# 1_P1.net
KiCad netlist of a schematic drawn in Altium Designer
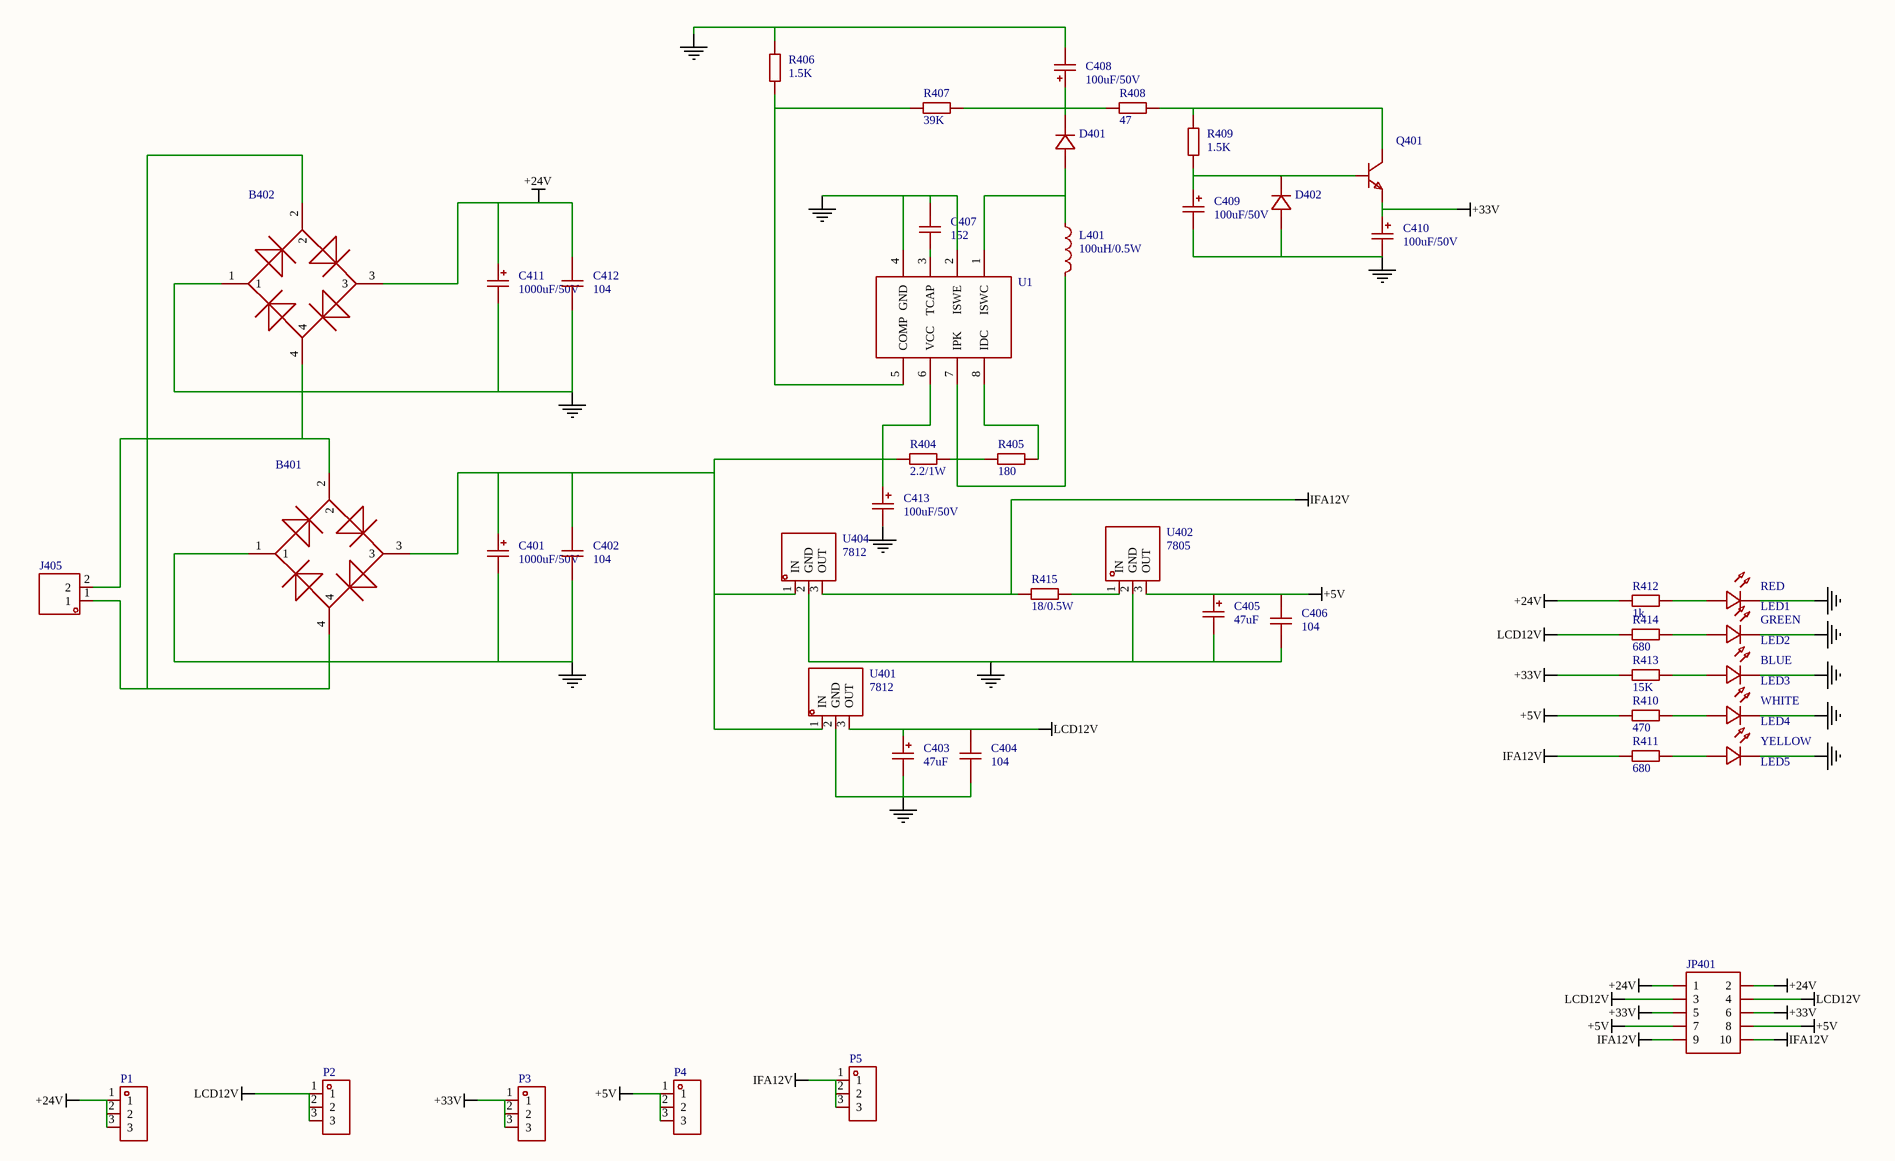
[diagram p0: 1_P1.schdoc]

(export (version "E")
  (design (tool "Eeschema 10.0.6"))
  (components
    (comp (ref "B401")
      (value "~")
      (footprint "B401/B402")
      (libsource (lib "altium-import") (part "root_0_整流桥_"))
    )
    (comp (ref "B402")
      (value "~")
      (footprint "B401/B402")
      (libsource (lib "altium-import") (part "root_0_整流桥_"))
    )
    (comp (ref "C401")
      (value "1000uF/50V")
      (footprint "C401/C411")
      (libsource (lib "altium-import") (part "root_1_C_Ele_SMD_3x5.4mm_"))
    )
    (comp (ref "C402")
      (value "104")
      (footprint "RAD-0.2")
      (libsource (lib "altium-import") (part "root_1_CAP_0603_"))
    )
    (comp (ref "C403")
      (value "47uF")
      (footprint "电解电容")
      (libsource (lib "altium-import") (part "root_1_C_Ele_SMD_3x5.4mm_"))
    )
    (comp (ref "C404")
      (value "104")
      (footprint "RAD-0.2")
      (libsource (lib "altium-import") (part "root_1_CAP_0603_"))
    )
    (comp (ref "C405")
      (value "47uF")
      (footprint "电解电容")
      (libsource (lib "altium-import") (part "root_1_C_Ele_SMD_3x5.4mm_"))
    )
    (comp (ref "C406")
      (value "104")
      (footprint "RAD-0.2")
      (libsource (lib "altium-import") (part "root_1_CAP_0603_"))
    )
    (comp (ref "C407")
      (value "152")
      (footprint "RAD-0.2")
      (libsource (lib "altium-import") (part "root_1_CAP_0603_"))
    )
    (comp (ref "C408")
      (value "100uF/50V")
      (footprint "电解电容")
      (libsource (lib "altium-import") (part "root_3_C_Ele_SMD_3x5.4mm_"))
    )
    (comp (ref "C409")
      (value "100uF/50V")
      (footprint "电解电容")
      (libsource (lib "altium-import") (part "root_1_C_Ele_SMD_3x5.4mm_"))
    )
    (comp (ref "C410")
      (value "100uF/50V")
      (footprint "电解电容")
      (libsource (lib "altium-import") (part "root_1_C_Ele_SMD_3x5.4mm_"))
    )
    (comp (ref "C411")
      (value "1000uF/50V")
      (footprint "C401/C411")
      (libsource (lib "altium-import") (part "root_1_C_Ele_SMD_3x5.4mm_"))
    )
    (comp (ref "C412")
      (value "104")
      (footprint "RAD-0.2")
      (libsource (lib "altium-import") (part "root_1_CAP_0603_"))
    )
    (comp (ref "C413")
      (value "100uF/50V")
      (footprint "电解电容")
      (libsource (lib "altium-import") (part "root_1_C_Ele_SMD_3x5.4mm_"))
    )
    (comp (ref "D401")
      (value "~")
      (footprint "D401/D402")
      (libsource (lib "altium-import") (part "root_1_D_1N4007A_"))
    )
    (comp (ref "D402")
      (value "~")
      (footprint "D401/D402")
      (libsource (lib "altium-import") (part "root_1_D_1N4007A_"))
    )
    (comp (ref "J405")
      (value "~")
      (footprint "J405")
      (fields (field (name "MANUFACTURER") "Ckmtw(灿科盟)") (field (name "MANUFACTURER PART") "B-2100S02P-A110"))
      (libsource (lib "altium-import") (part "root_2_HDR-M_2.54_1x2P_"))
    )
    (comp (ref "JP401")
      (value "~")
      (footprint "JP401")
      (libsource (lib "altium-import") (part "root_0_HDR-F_2.54_2x5_"))
    )
    (comp (ref "L401")
      (value "100uH/0.5W")
      (footprint "L401")
      (libsource (lib "altium-import") (part "root_3_L_0603_"))
    )
    (comp (ref "LED1")
      (value "RED")
      (footprint "LED")
      (libsource (lib "altium-import") (part "root_0_LED_TH-R_3mm_"))
    )
    (comp (ref "LED2")
      (value "GREEN")
      (footprint "LED")
      (libsource (lib "altium-import") (part "root_0_LED_TH-R_3mm_"))
    )
    (comp (ref "LED3")
      (value "BLUE")
      (footprint "LED")
      (libsource (lib "altium-import") (part "root_0_LED_TH-R_3mm_"))
    )
    (comp (ref "LED4")
      (value "WHITE")
      (footprint "LED")
      (libsource (lib "altium-import") (part "root_0_LED_TH-R_3mm_"))
    )
    (comp (ref "LED5")
      (value "YELLOW")
      (footprint "LED")
      (libsource (lib "altium-import") (part "root_0_LED_TH-R_3mm_"))
    )
    (comp (ref "P1")
      (value "~")
      (footprint "HDR-TH_3P-P2.54-V-F")
      (libsource (lib "altium-import") (part "root_0_HDR-F_2.54_1x3P_"))
    )
    (comp (ref "P2")
      (value "~")
      (footprint "HDR-TH_3P-P2.54-V-F")
      (libsource (lib "altium-import") (part "root_0_HDR-F_2.54_1x3P_"))
    )
    (comp (ref "P3")
      (value "~")
      (footprint "HDR-TH_3P-P2.54-V-F")
      (libsource (lib "altium-import") (part "root_0_HDR-F_2.54_1x3P_"))
    )
    (comp (ref "P4")
      (value "~")
      (footprint "HDR-TH_3P-P2.54-V-F")
      (libsource (lib "altium-import") (part "root_0_HDR-F_2.54_1x3P_"))
    )
    (comp (ref "P5")
      (value "~")
      (footprint "HDR-TH_3P-P2.54-V-F")
      (libsource (lib "altium-import") (part "root_0_HDR-F_2.54_1x3P_"))
    )
    (comp (ref "Q401")
      (value "~")
      (footprint "Q401")
      (libsource (lib "altium-import") (part "root_0_S8050_SOT_NPN_"))
    )
    (comp (ref "R404")
      (value "2.2/1W")
      (footprint "Res_1/2W")
      (libsource (lib "altium-import") (part "root_2_Res_AXIAL-1/4W_"))
    )
    (comp (ref "R405")
      (value "180")
      (footprint "Res_1/4W")
      (libsource (lib "altium-import") (part "root_0_Res_AXIAL-1/4W_"))
    )
    (comp (ref "R406")
      (value "1.5K")
      (footprint "Res_1/4W")
      (libsource (lib "altium-import") (part "root_1_Res_AXIAL-1/4W_"))
    )
    (comp (ref "R407")
      (value "39K")
      (footprint "Res_1/4W")
      (libsource (lib "altium-import") (part "root_0_Res_AXIAL-1/4W_"))
    )
    (comp (ref "R408")
      (value "47")
      (footprint "Res_1/4W")
      (libsource (lib "altium-import") (part "root_0_Res_AXIAL-1/4W_"))
    )
    (comp (ref "R409")
      (value "1.5K")
      (footprint "Res_1/4W")
      (libsource (lib "altium-import") (part "root_1_Res_AXIAL-1/4W_"))
    )
    (comp (ref "R410")
      (value "470")
      (footprint "Res_1/4W")
      (libsource (lib "altium-import") (part "root_0_Res_AXIAL-1/4W_"))
    )
    (comp (ref "R411")
      (value "680")
      (footprint "Res_1/4W")
      (libsource (lib "altium-import") (part "root_0_Res_AXIAL-1/4W_"))
    )
    (comp (ref "R412")
      (value "1k")
      (footprint "Res_1/4W")
      (libsource (lib "altium-import") (part "root_0_Res_AXIAL-1/4W_"))
    )
    (comp (ref "R413")
      (value "15K")
      (footprint "Res_1/4W")
      (libsource (lib "altium-import") (part "root_0_Res_AXIAL-1/4W_"))
    )
    (comp (ref "R414")
      (value "680")
      (footprint "Res_1/4W")
      (libsource (lib "altium-import") (part "root_0_Res_AXIAL-1/4W_"))
    )
    (comp (ref "R415")
      (value "18/0.5W")
      (footprint "Res_1/2W")
      (libsource (lib "altium-import") (part "root_2_Res_AXIAL-1/4W_"))
    )
    (comp (ref "U1")
      (value "~")
      (footprint "DIP-8_L10.0-W6.5-P2.54-LS7.6-BL-A")
      (libsource (lib "altium-import") (part "root_1_MC34063_"))
    )
    (comp (ref "U401")
      (value "7812")
      (footprint "U401/U402/U404")
      (fields (field (name "MANUFACTURER") "BLUE ROCKET(蓝箭)"))
      (libsource (lib "altium-import") (part "root_1_7812_"))
    )
    (comp (ref "U402")
      (value "7805")
      (footprint "U401/U402/U404")
      (fields (field (name "MANUFACTURER") "SY(顺烨）"))
      (libsource (lib "altium-import") (part "root_1_7805_"))
    )
    (comp (ref "U404")
      (value "7812")
      (footprint "U401/U402/U404")
      (fields (field (name "MANUFACTURER") "BLUE ROCKET(蓝箭)"))
      (libsource (lib "altium-import") (part "root_1_7812_"))
    )
  )
  (nets
    (net (code "1") (name "+5V") (class "Default")
      (node (ref "C405") (pin "1") (pinfunction "1_1") (pintype "passive"))
      (node (ref "C406") (pin "2") (pinfunction "2_2") (pintype "passive"))
      (node (ref "JP401") (pin "7") (pinfunction "7_7") (pintype "passive"))
      (node (ref "JP401") (pin "8") (pinfunction "8_8") (pintype "passive"))
      (node (ref "P4") (pin "1") (pinfunction "1_1") (pintype "passive"))
      (node (ref "P4") (pin "2") (pinfunction "2_2") (pintype "passive"))
      (node (ref "P4") (pin "3") (pinfunction "3_3") (pintype "passive"))
      (node (ref "R410") (pin "1") (pinfunction "1_1") (pintype "passive"))
      (node (ref "U402") (pin "3") (pinfunction "OUT_3") (pintype "passive"))
    )
    (net (code "2") (name "+24V") (class "Default")
      (node (ref "B402") (pin "3") (pinfunction "3_3") (pintype "passive"))
      (node (ref "C411") (pin "1") (pinfunction "1_1") (pintype "passive"))
      (node (ref "C412") (pin "2") (pinfunction "2_2") (pintype "passive"))
      (node (ref "JP401") (pin "1") (pinfunction "1_1") (pintype "passive"))
      (node (ref "JP401") (pin "2") (pinfunction "2_2") (pintype "passive"))
      (node (ref "P1") (pin "1") (pinfunction "1_1") (pintype "passive"))
      (node (ref "P1") (pin "2") (pinfunction "2_2") (pintype "passive"))
      (node (ref "P1") (pin "3") (pinfunction "3_3") (pintype "passive"))
      (node (ref "R412") (pin "1") (pinfunction "1_1") (pintype "passive"))
    )
    (net (code "3") (name "+33V") (class "Default")
      (node (ref "C410") (pin "1") (pinfunction "1_1") (pintype "passive"))
      (node (ref "JP401") (pin "5") (pinfunction "5_5") (pintype "passive"))
      (node (ref "JP401") (pin "6") (pinfunction "6_6") (pintype "passive"))
      (node (ref "P3") (pin "1") (pinfunction "1_1") (pintype "passive"))
      (node (ref "P3") (pin "2") (pinfunction "2_2") (pintype "passive"))
      (node (ref "P3") (pin "3") (pinfunction "3_3") (pintype "passive"))
      (node (ref "Q401") (pin "1") (pinfunction "1_1") (pintype "passive"))
      (node (ref "R413") (pin "1") (pinfunction "1_1") (pintype "passive"))
    )
    (net (code "4") (name "GND") (class "Default")
      (node (ref "B401") (pin "1") (pinfunction "1_1") (pintype "passive"))
      (node (ref "B402") (pin "1") (pinfunction "1_1") (pintype "passive"))
      (node (ref "C401") (pin "2") (pinfunction "2_2") (pintype "passive"))
      (node (ref "C402") (pin "1") (pinfunction "1_1") (pintype "passive"))
      (node (ref "C403") (pin "2") (pinfunction "2_2") (pintype "passive"))
      (node (ref "C404") (pin "1") (pinfunction "1_1") (pintype "passive"))
      (node (ref "C405") (pin "2") (pinfunction "2_2") (pintype "passive"))
      (node (ref "C406") (pin "1") (pinfunction "1_1") (pintype "passive"))
      (node (ref "C407") (pin "2") (pinfunction "2_2") (pintype "passive"))
      (node (ref "C408") (pin "2") (pinfunction "2_2") (pintype "passive"))
      (node (ref "C409") (pin "2") (pinfunction "2_2") (pintype "passive"))
      (node (ref "C410") (pin "2") (pinfunction "2_2") (pintype "passive"))
      (node (ref "C411") (pin "2") (pinfunction "2_2") (pintype "passive"))
      (node (ref "C412") (pin "1") (pinfunction "1_1") (pintype "passive"))
      (node (ref "C413") (pin "2") (pinfunction "2_2") (pintype "passive"))
      (node (ref "D402") (pin "2") (pinfunction "A_2") (pintype "passive"))
      (node (ref "LED1") (pin "2") (pinfunction "A_2") (pintype "passive"))
      (node (ref "LED2") (pin "2") (pinfunction "A_2") (pintype "passive"))
      (node (ref "LED3") (pin "2") (pinfunction "A_2") (pintype "passive"))
      (node (ref "LED4") (pin "2") (pinfunction "A_2") (pintype "passive"))
      (node (ref "LED5") (pin "2") (pinfunction "A_2") (pintype "passive"))
      (node (ref "R406") (pin "2") (pinfunction "2_2") (pintype "passive"))
      (node (ref "U1") (pin "2") (pinfunction "ISWE_2") (pintype "passive"))
      (node (ref "U1") (pin "4") (pinfunction "GND_4") (pintype "passive"))
      (node (ref "U401") (pin "2") (pinfunction "GND_2") (pintype "passive"))
      (node (ref "U402") (pin "2") (pinfunction "GND_2") (pintype "passive"))
      (node (ref "U404") (pin "2") (pinfunction "GND_2") (pintype "passive"))
    )
    (net (code "5") (name "IFA12V") (class "Default")
      (node (ref "JP401") (pin "10") (pinfunction "10_10") (pintype "passive"))
      (node (ref "JP401") (pin "9") (pinfunction "9_9") (pintype "passive"))
      (node (ref "P5") (pin "1") (pinfunction "1_1") (pintype "passive"))
      (node (ref "P5") (pin "2") (pinfunction "2_2") (pintype "passive"))
      (node (ref "P5") (pin "3") (pinfunction "3_3") (pintype "passive"))
      (node (ref "R411") (pin "1") (pinfunction "1_1") (pintype "passive"))
      (node (ref "R415") (pin "2") (pinfunction "2_2") (pintype "passive"))
      (node (ref "U404") (pin "3") (pinfunction "OUT_3") (pintype "passive"))
    )
    (net (code "6") (name "LCD12V") (class "Default")
      (node (ref "C403") (pin "1") (pinfunction "1_1") (pintype "passive"))
      (node (ref "C404") (pin "2") (pinfunction "2_2") (pintype "passive"))
      (node (ref "JP401") (pin "3") (pinfunction "3_3") (pintype "passive"))
      (node (ref "JP401") (pin "4") (pinfunction "4_4") (pintype "passive"))
      (node (ref "P2") (pin "1") (pinfunction "1_1") (pintype "passive"))
      (node (ref "P2") (pin "2") (pinfunction "2_2") (pintype "passive"))
      (node (ref "P2") (pin "3") (pinfunction "3_3") (pintype "passive"))
      (node (ref "R414") (pin "1") (pinfunction "1_1") (pintype "passive"))
      (node (ref "U401") (pin "3") (pinfunction "OUT_3") (pintype "passive"))
    )
    (net (code "7") (name "Net-(B401-Pad2)") (class "Default")
      (node (ref "B401") (pin "2") (pinfunction "2_2") (pintype "passive"))
      (node (ref "B402") (pin "4") (pinfunction "4_4") (pintype "passive"))
      (node (ref "J405") (pin "2") (pinfunction "2_2") (pintype "passive"))
    )
    (net (code "8") (name "Net-(B401-Pad4)") (class "Default")
      (node (ref "B401") (pin "4") (pinfunction "4_4") (pintype "passive"))
      (node (ref "B402") (pin "2") (pinfunction "2_2") (pintype "passive"))
      (node (ref "J405") (pin "1") (pinfunction "1_1") (pintype "passive"))
    )
    (net (code "9") (name "Net-(D401-A)") (class "Default")
      (node (ref "D401") (pin "2") (pinfunction "A_2") (pintype "passive"))
      (node (ref "L401") (pin "1") (pinfunction "1_1") (pintype "passive"))
      (node (ref "U1") (pin "1") (pinfunction "ISWC_1") (pintype "passive"))
    )
    (net (code "10") (name "Net-(D401-K)") (class "Default")
      (node (ref "C408") (pin "1") (pinfunction "1_1") (pintype "passive"))
      (node (ref "D401") (pin "1") (pinfunction "K_1") (pintype "passive"))
      (node (ref "R407") (pin "2") (pinfunction "2_2") (pintype "passive"))
      (node (ref "R408") (pin "1") (pinfunction "1_1") (pintype "passive"))
    )
    (net (code "11") (name "Net-(D402-K)") (class "Default")
      (node (ref "C409") (pin "1") (pinfunction "1_1") (pintype "passive"))
      (node (ref "D402") (pin "1") (pinfunction "K_1") (pintype "passive"))
      (node (ref "Q401") (pin "3") (pinfunction "3_3") (pintype "passive"))
      (node (ref "R409") (pin "1") (pinfunction "1_1") (pintype "passive"))
    )
    (net (code "12") (name "Net-(LED1-C)") (class "Default")
      (node (ref "LED1") (pin "1") (pinfunction "C_1") (pintype "passive"))
      (node (ref "R412") (pin "2") (pinfunction "2_2") (pintype "passive"))
    )
    (net (code "13") (name "Net-(LED2-C)") (class "Default")
      (node (ref "LED2") (pin "1") (pinfunction "C_1") (pintype "passive"))
      (node (ref "R414") (pin "2") (pinfunction "2_2") (pintype "passive"))
    )
    (net (code "14") (name "Net-(LED3-C)") (class "Default")
      (node (ref "LED3") (pin "1") (pinfunction "C_1") (pintype "passive"))
      (node (ref "R413") (pin "2") (pinfunction "2_2") (pintype "passive"))
    )
    (net (code "15") (name "Net-(LED4-C)") (class "Default")
      (node (ref "LED4") (pin "1") (pinfunction "C_1") (pintype "passive"))
      (node (ref "R410") (pin "2") (pinfunction "2_2") (pintype "passive"))
    )
    (net (code "16") (name "Net-(LED5-C)") (class "Default")
      (node (ref "LED5") (pin "1") (pinfunction "C_1") (pintype "passive"))
      (node (ref "R411") (pin "2") (pinfunction "2_2") (pintype "passive"))
    )
    (net (code "17") (name "Net-(Q401-Pad2)") (class "Default")
      (node (ref "Q401") (pin "2") (pinfunction "2_2") (pintype "passive"))
      (node (ref "R408") (pin "2") (pinfunction "2_2") (pintype "passive"))
      (node (ref "R409") (pin "2") (pinfunction "2_2") (pintype "passive"))
    )
    (net (code "18") (name "Net-(U1-COMP)") (class "Default")
      (node (ref "R406") (pin "1") (pinfunction "1_1") (pintype "passive"))
      (node (ref "R407") (pin "1") (pinfunction "1_1") (pintype "passive"))
      (node (ref "U1") (pin "5") (pinfunction "COMP_5") (pintype "passive"))
    )
    (net (code "19") (name "Net-(U1-IDC)") (class "Default")
      (node (ref "R405") (pin "2") (pinfunction "2_2") (pintype "passive"))
      (node (ref "U1") (pin "8") (pinfunction "IDC_8") (pintype "passive"))
    )
    (net (code "20") (name "Net-(U1-IPK)") (class "Default")
      (node (ref "L401") (pin "2") (pinfunction "2_2") (pintype "passive"))
      (node (ref "R404") (pin "1") (pinfunction "1_1") (pintype "passive"))
      (node (ref "R405") (pin "1") (pinfunction "1_1") (pintype "passive"))
      (node (ref "U1") (pin "7") (pinfunction "IPK_7") (pintype "passive"))
    )
    (net (code "21") (name "Net-(U1-TCAP)") (class "Default")
      (node (ref "C407") (pin "1") (pinfunction "1_1") (pintype "passive"))
      (node (ref "U1") (pin "3") (pinfunction "TCAP_3") (pintype "passive"))
    )
    (net (code "22") (name "Net-(U1-VCC)") (class "Default")
      (node (ref "B401") (pin "3") (pinfunction "3_3") (pintype "passive"))
      (node (ref "C401") (pin "1") (pinfunction "1_1") (pintype "passive"))
      (node (ref "C402") (pin "2") (pinfunction "2_2") (pintype "passive"))
      (node (ref "C413") (pin "1") (pinfunction "1_1") (pintype "passive"))
      (node (ref "R404") (pin "2") (pinfunction "2_2") (pintype "passive"))
      (node (ref "U1") (pin "6") (pinfunction "VCC_6") (pintype "passive"))
      (node (ref "U401") (pin "1") (pinfunction "IN_1") (pintype "passive"))
      (node (ref "U404") (pin "1") (pinfunction "IN_1") (pintype "passive"))
    )
    (net (code "23") (name "Net-(U402-IN)") (class "Default")
      (node (ref "R415") (pin "1") (pinfunction "1_1") (pintype "passive"))
      (node (ref "U402") (pin "1") (pinfunction "IN_1") (pintype "passive"))
    )
  )
)
